# PowerKit.net
KiCad netlist of a schematic drawn in EAGLE
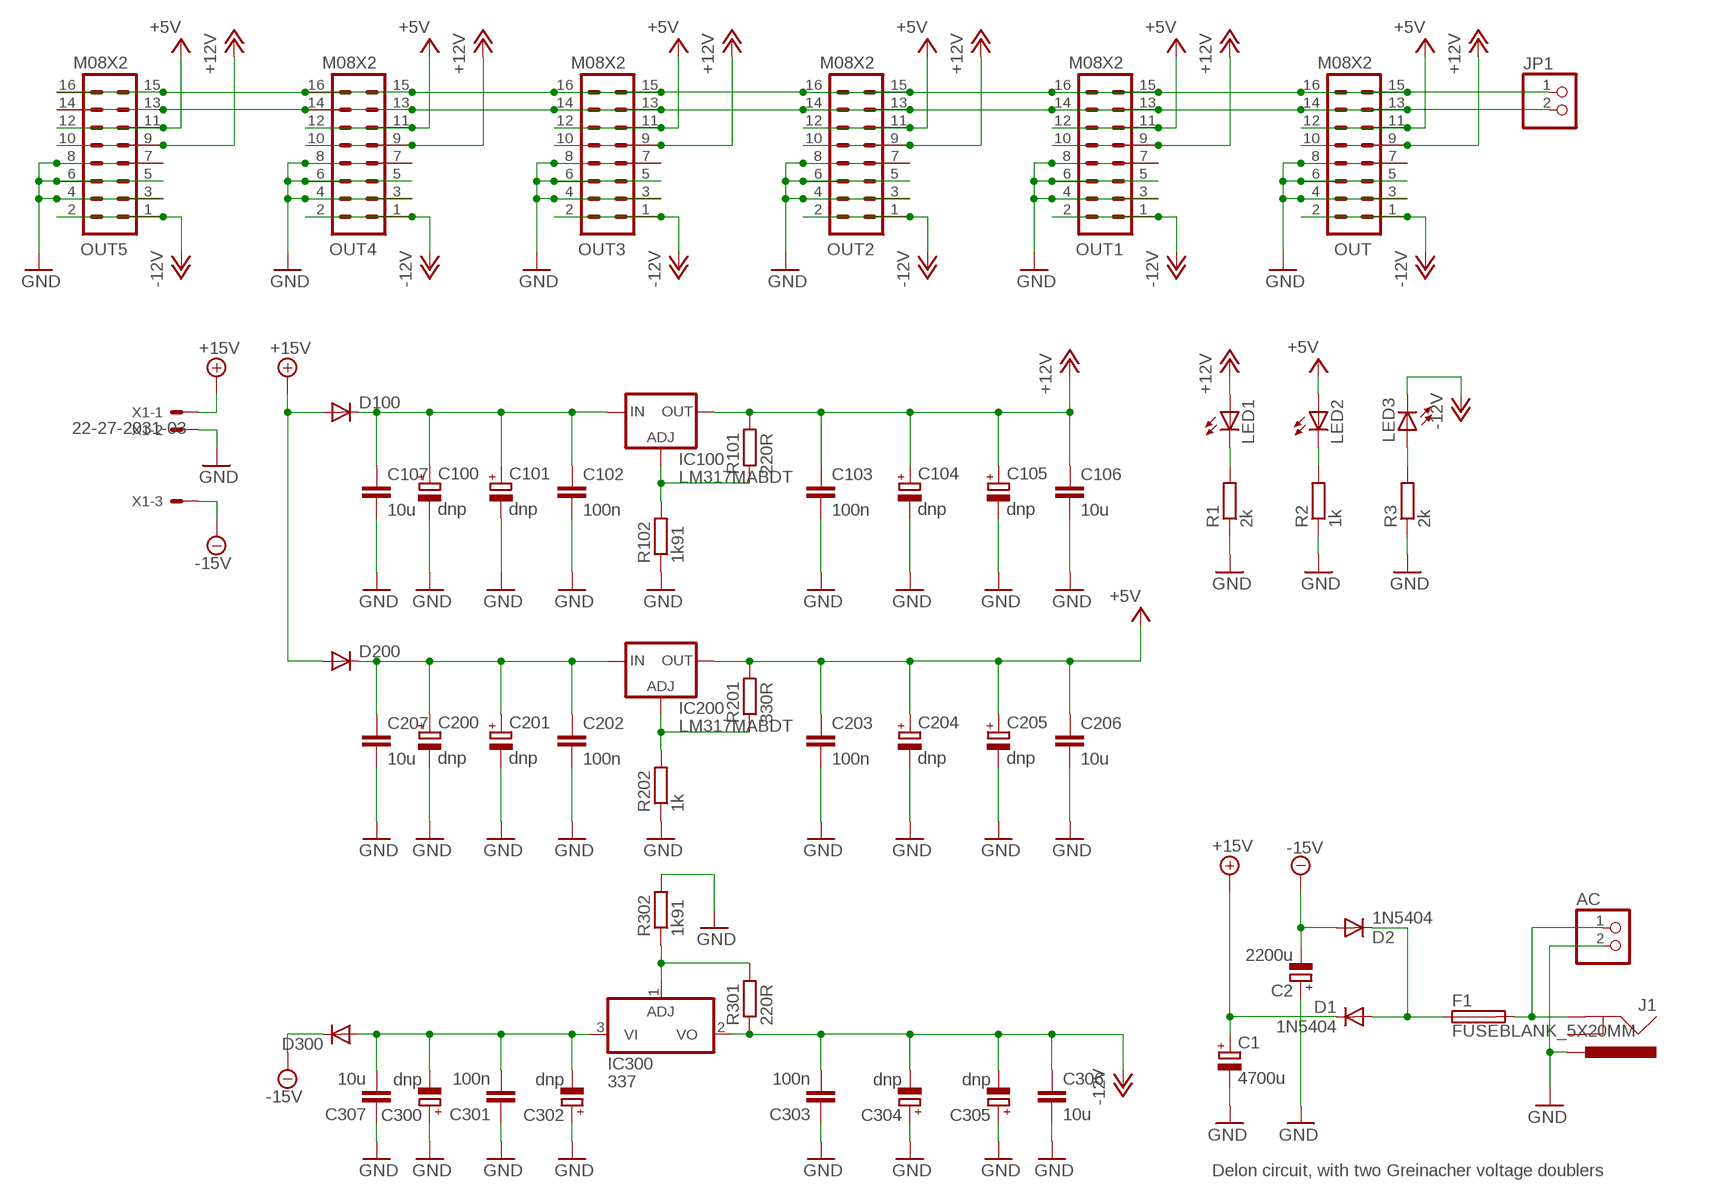
[diagram p0: schematic, sheet 1]

(export (version "E")
  (design (tool "Eeschema 10.0.6"))
  (components
    (comp (ref "AC")
      (value "PINHD-1X2")
      (footprint "eagle-import:1X02")
      (libsource (lib "eagle-import") (part "PINHD-1X2"))
    )
    (comp (ref "C1")
      (value "4700u")
      (footprint "eagle-import:E7,5-18")
      (libsource (lib "eagle-import") (part "resistor_CPOL-EUE7.5-18"))
    )
    (comp (ref "C2")
      (value "2200u")
      (footprint "eagle-import:E7,5-18")
      (libsource (lib "eagle-import") (part "resistor_CPOL-EUE7.5-18"))
    )
    (comp (ref "C100")
      (value "dnp")
      (footprint "eagle-import:E5-8,5")
      (libsource (lib "eagle-import") (part "CPOL-EUE5-8.5"))
    )
    (comp (ref "C101")
      (value "dnp")
      (footprint "eagle-import:153CLV-0810")
      (libsource (lib "eagle-import") (part "CPOL-EU153CLV-0810"))
    )
    (comp (ref "C102")
      (value "100n")
      (footprint "eagle-import:C0603")
      (libsource (lib "eagle-import") (part "C-EUC0603"))
    )
    (comp (ref "C103")
      (value "100n")
      (footprint "eagle-import:C0603")
      (libsource (lib "eagle-import") (part "C-EUC0603"))
    )
    (comp (ref "C104")
      (value "dnp")
      (footprint "eagle-import:153CLV-0810")
      (libsource (lib "eagle-import") (part "CPOL-EU153CLV-0810"))
    )
    (comp (ref "C105")
      (value "dnp")
      (footprint "eagle-import:E5-8,5")
      (libsource (lib "eagle-import") (part "CPOL-EUE5-8.5"))
    )
    (comp (ref "C106")
      (value "10u")
      (footprint "eagle-import:C1206")
      (libsource (lib "eagle-import") (part "C-EUC1206"))
    )
    (comp (ref "C107")
      (value "10u")
      (footprint "eagle-import:C1206")
      (libsource (lib "eagle-import") (part "C-EUC1206"))
    )
    (comp (ref "C200")
      (value "dnp")
      (footprint "eagle-import:E5-8,5")
      (libsource (lib "eagle-import") (part "CPOL-EUE5-8.5"))
    )
    (comp (ref "C201")
      (value "dnp")
      (footprint "eagle-import:153CLV-0810")
      (libsource (lib "eagle-import") (part "CPOL-EU153CLV-0810"))
    )
    (comp (ref "C202")
      (value "100n")
      (footprint "eagle-import:C0603")
      (libsource (lib "eagle-import") (part "C-EUC0603"))
    )
    (comp (ref "C203")
      (value "100n")
      (footprint "eagle-import:C0603")
      (libsource (lib "eagle-import") (part "C-EUC0603"))
    )
    (comp (ref "C204")
      (value "dnp")
      (footprint "eagle-import:153CLV-0810")
      (libsource (lib "eagle-import") (part "CPOL-EU153CLV-0810"))
    )
    (comp (ref "C205")
      (value "dnp")
      (footprint "eagle-import:E5-8,5")
      (libsource (lib "eagle-import") (part "CPOL-EUE5-8.5"))
    )
    (comp (ref "C206")
      (value "10u")
      (footprint "eagle-import:C1206")
      (libsource (lib "eagle-import") (part "C-EUC1206"))
    )
    (comp (ref "C207")
      (value "10u")
      (footprint "eagle-import:C1206")
      (libsource (lib "eagle-import") (part "C-EUC1206"))
    )
    (comp (ref "C300")
      (value "dnp")
      (footprint "eagle-import:E5-8,5")
      (libsource (lib "eagle-import") (part "CPOL-EUE5-8.5"))
    )
    (comp (ref "C301")
      (value "100n")
      (footprint "eagle-import:C0603")
      (libsource (lib "eagle-import") (part "C-EUC0603"))
    )
    (comp (ref "C302")
      (value "dnp")
      (footprint "eagle-import:153CLV-0810")
      (libsource (lib "eagle-import") (part "CPOL-EU153CLV-0810"))
    )
    (comp (ref "C303")
      (value "100n")
      (footprint "eagle-import:C0603")
      (libsource (lib "eagle-import") (part "C-EUC0603"))
    )
    (comp (ref "C304")
      (value "dnp")
      (footprint "eagle-import:153CLV-0810")
      (libsource (lib "eagle-import") (part "CPOL-EU153CLV-0810"))
    )
    (comp (ref "C305")
      (value "dnp")
      (footprint "eagle-import:E5-8,5")
      (libsource (lib "eagle-import") (part "CPOL-EUE5-8.5"))
    )
    (comp (ref "C306")
      (value "10u")
      (footprint "eagle-import:C1206")
      (libsource (lib "eagle-import") (part "C-EUC1206"))
    )
    (comp (ref "C307")
      (value "10u")
      (footprint "eagle-import:C1206")
      (libsource (lib "eagle-import") (part "C-EUC1206"))
    )
    (comp (ref "D1")
      (value "1N5404")
      (footprint "eagle-import:DIODE-1N4001")
      (libsource (lib "eagle-import") (part "DIODE1N4001"))
    )
    (comp (ref "D2")
      (value "1N5404")
      (footprint "eagle-import:DIODE-1N4001")
      (libsource (lib "eagle-import") (part "DIODE1N4001"))
    )
    (comp (ref "D100")
      (value "DIODESMA")
      (footprint "eagle-import:SMA-DIODE")
      (libsource (lib "eagle-import") (part "DIODESMA"))
    )
    (comp (ref "D200")
      (value "DIODESMA")
      (footprint "eagle-import:SMA-DIODE")
      (libsource (lib "eagle-import") (part "DIODESMA"))
    )
    (comp (ref "D300")
      (value "DIODESMA")
      (footprint "eagle-import:SMA-DIODE")
      (libsource (lib "eagle-import") (part "DIODESMA"))
    )
    (comp (ref "F1")
      (value "FUSEBLANK_5X20MM")
      (footprint "eagle-import:FUSE_HOLDER_5X20MM")
      (libsource (lib "eagle-import") (part "FUSEBLANK_5X20MM"))
    )
    (comp (ref "IC100")
      (value "LM317MABDT")
      (footprint "eagle-import:DPACK")
      (libsource (lib "eagle-import") (part "v-reg_LM317?MABDT"))
    )
    (comp (ref "IC200")
      (value "LM317MABDT")
      (footprint "eagle-import:DPACK")
      (libsource (lib "eagle-import") (part "v-reg_LM317?MABDT"))
    )
    (comp (ref "IC300")
      (value "337")
      (footprint "eagle-import:TO252")
      (libsource (lib "eagle-import") (part "337"))
    )
    (comp (ref "J1")
      (value "POWER_JACKPTH")
      (footprint "eagle-import:POWER_JACK_PTH")
      (libsource (lib "eagle-import") (part "POWER_JACKPTH"))
    )
    (comp (ref "JP1")
      (value "PINHD-1X2")
      (footprint "eagle-import:1X02")
      (libsource (lib "eagle-import") (part "PINHD-1X2"))
    )
    (comp (ref "LED1")
      (value "LEDCHIPLED_1206")
      (footprint "eagle-import:CHIPLED_1206")
      (libsource (lib "eagle-import") (part "LEDCHIPLED_1206"))
    )
    (comp (ref "LED2")
      (value "LEDCHIPLED_1206")
      (footprint "eagle-import:CHIPLED_1206")
      (libsource (lib "eagle-import") (part "LEDCHIPLED_1206"))
    )
    (comp (ref "LED3")
      (value "LEDCHIPLED_1206")
      (footprint "eagle-import:CHIPLED_1206")
      (libsource (lib "eagle-import") (part "LEDCHIPLED_1206"))
    )
    (comp (ref "OUT")
      (value "M08X2")
      (footprint "eagle-import:2X8")
      (libsource (lib "eagle-import") (part "M08X2"))
    )
    (comp (ref "OUT1")
      (value "M08X2")
      (footprint "eagle-import:2X8")
      (libsource (lib "eagle-import") (part "M08X2"))
    )
    (comp (ref "OUT2")
      (value "M08X2")
      (footprint "eagle-import:2X8")
      (libsource (lib "eagle-import") (part "M08X2"))
    )
    (comp (ref "OUT3")
      (value "M08X2")
      (footprint "eagle-import:2X8")
      (libsource (lib "eagle-import") (part "M08X2"))
    )
    (comp (ref "OUT4")
      (value "M08X2")
      (footprint "eagle-import:2X8")
      (libsource (lib "eagle-import") (part "M08X2"))
    )
    (comp (ref "OUT5")
      (value "M08X2")
      (footprint "eagle-import:2X8")
      (libsource (lib "eagle-import") (part "M08X2"))
    )
    (comp (ref "R1")
      (value "2k")
      (footprint "eagle-import:0603")
      (libsource (lib "eagle-import") (part "R-EU_0603"))
    )
    (comp (ref "R2")
      (value "1k")
      (footprint "eagle-import:0603")
      (libsource (lib "eagle-import") (part "R-EU_0603"))
    )
    (comp (ref "R3")
      (value "2k")
      (footprint "eagle-import:0603")
      (libsource (lib "eagle-import") (part "R-EU_0603"))
    )
    (comp (ref "R101")
      (value "220R")
      (footprint "eagle-import:0603")
      (libsource (lib "eagle-import") (part "R-EU_0603"))
    )
    (comp (ref "R102")
      (value "1k91")
      (footprint "eagle-import:0603")
      (libsource (lib "eagle-import") (part "R-EU_0603"))
    )
    (comp (ref "R201")
      (value "330R")
      (footprint "eagle-import:0603")
      (libsource (lib "eagle-import") (part "R-EU_0603"))
    )
    (comp (ref "R202")
      (value "1k")
      (footprint "eagle-import:0603")
      (libsource (lib "eagle-import") (part "R-EU_0603"))
    )
    (comp (ref "R301")
      (value "220R")
      (footprint "eagle-import:0603")
      (libsource (lib "eagle-import") (part "R-EU_0603"))
    )
    (comp (ref "R302")
      (value "1k91")
      (footprint "eagle-import:0603")
      (libsource (lib "eagle-import") (part "R-EU_0603"))
    )
    (comp (ref "X1")
      (value "22-27-2031-03")
      (footprint "eagle-import:6410-03")
      (libsource (lib "eagle-import") (part "22-?-0327-2031"))
    )
  )
  (nets
    (net (code "1") (name "+5V") (class "Default")
      (node (ref "C203") (pin "1") (pinfunction "1_1") (pintype "passive"))
      (node (ref "C204") (pin "+") (pinfunction "+_+") (pintype "passive"))
      (node (ref "C205") (pin "+") (pinfunction "+_+") (pintype "passive"))
      (node (ref "C206") (pin "1") (pinfunction "1_1") (pintype "passive"))
      (node (ref "IC200") (pin "4") (pinfunction "OUT_4") (pintype "passive"))
      (node (ref "LED2") (pin "A") (pinfunction "A_A") (pintype "passive"))
      (node (ref "OUT") (pin "11") (pinfunction "11_11") (pintype "passive"))
      (node (ref "OUT") (pin "12") (pinfunction "12_12") (pintype "passive"))
      (node (ref "OUT1") (pin "11") (pinfunction "11_11") (pintype "passive"))
      (node (ref "OUT1") (pin "12") (pinfunction "12_12") (pintype "passive"))
      (node (ref "OUT2") (pin "11") (pinfunction "11_11") (pintype "passive"))
      (node (ref "OUT2") (pin "12") (pinfunction "12_12") (pintype "passive"))
      (node (ref "OUT3") (pin "11") (pinfunction "11_11") (pintype "passive"))
      (node (ref "OUT3") (pin "12") (pinfunction "12_12") (pintype "passive"))
      (node (ref "OUT4") (pin "11") (pinfunction "11_11") (pintype "passive"))
      (node (ref "OUT4") (pin "12") (pinfunction "12_12") (pintype "passive"))
      (node (ref "OUT5") (pin "11") (pinfunction "11_11") (pintype "passive"))
      (node (ref "OUT5") (pin "12") (pinfunction "12_12") (pintype "passive"))
      (node (ref "R201") (pin "2") (pinfunction "2_2") (pintype "passive"))
    )
    (net (code "2") (name "+12V") (class "Default")
      (node (ref "C103") (pin "1") (pinfunction "1_1") (pintype "passive"))
      (node (ref "C104") (pin "+") (pinfunction "+_+") (pintype "passive"))
      (node (ref "C105") (pin "+") (pinfunction "+_+") (pintype "passive"))
      (node (ref "C106") (pin "1") (pinfunction "1_1") (pintype "passive"))
      (node (ref "IC100") (pin "4") (pinfunction "OUT_4") (pintype "passive"))
      (node (ref "LED1") (pin "A") (pinfunction "A_A") (pintype "passive"))
      (node (ref "OUT") (pin "10") (pinfunction "10_10") (pintype "passive"))
      (node (ref "OUT") (pin "9") (pinfunction "9_9") (pintype "passive"))
      (node (ref "OUT1") (pin "10") (pinfunction "10_10") (pintype "passive"))
      (node (ref "OUT1") (pin "9") (pinfunction "9_9") (pintype "passive"))
      (node (ref "OUT2") (pin "10") (pinfunction "10_10") (pintype "passive"))
      (node (ref "OUT2") (pin "9") (pinfunction "9_9") (pintype "passive"))
      (node (ref "OUT3") (pin "10") (pinfunction "10_10") (pintype "passive"))
      (node (ref "OUT3") (pin "9") (pinfunction "9_9") (pintype "passive"))
      (node (ref "OUT4") (pin "10") (pinfunction "10_10") (pintype "passive"))
      (node (ref "OUT4") (pin "9") (pinfunction "9_9") (pintype "passive"))
      (node (ref "OUT5") (pin "10") (pinfunction "10_10") (pintype "passive"))
      (node (ref "OUT5") (pin "9") (pinfunction "9_9") (pintype "passive"))
      (node (ref "R101") (pin "2") (pinfunction "2_2") (pintype "passive"))
    )
    (net (code "3") (name "+15V") (class "Default")
      (node (ref "C1") (pin "+") (pinfunction "+_+") (pintype "passive"))
      (node (ref "D1") (pin "C") (pinfunction "C_C") (pintype "passive"))
      (node (ref "D100") (pin "A") (pinfunction "A_A") (pintype "passive"))
      (node (ref "D200") (pin "A") (pinfunction "A_A") (pintype "passive"))
      (node (ref "X1") (pin "1") (pinfunction "S_1") (pintype "passive"))
    )
    (net (code "4") (name "-12V") (class "Default")
      (node (ref "C303") (pin "2") (pinfunction "2_2") (pintype "passive"))
      (node (ref "C304") (pin "-") (pinfunction "-_-") (pintype "passive"))
      (node (ref "C305") (pin "-") (pinfunction "-_-") (pintype "passive"))
      (node (ref "C306") (pin "1") (pinfunction "1_1") (pintype "passive"))
      (node (ref "IC300") (pin "2") (pinfunction "VO_2") (pintype "passive"))
      (node (ref "LED3") (pin "C") (pinfunction "C_C") (pintype "passive"))
      (node (ref "OUT") (pin "1") (pinfunction "1_1") (pintype "passive"))
      (node (ref "OUT") (pin "2") (pinfunction "2_2") (pintype "passive"))
      (node (ref "OUT1") (pin "1") (pinfunction "1_1") (pintype "passive"))
      (node (ref "OUT1") (pin "2") (pinfunction "2_2") (pintype "passive"))
      (node (ref "OUT2") (pin "1") (pinfunction "1_1") (pintype "passive"))
      (node (ref "OUT2") (pin "2") (pinfunction "2_2") (pintype "passive"))
      (node (ref "OUT3") (pin "1") (pinfunction "1_1") (pintype "passive"))
      (node (ref "OUT3") (pin "2") (pinfunction "2_2") (pintype "passive"))
      (node (ref "OUT4") (pin "1") (pinfunction "1_1") (pintype "passive"))
      (node (ref "OUT4") (pin "2") (pinfunction "2_2") (pintype "passive"))
      (node (ref "OUT5") (pin "1") (pinfunction "1_1") (pintype "passive"))
      (node (ref "OUT5") (pin "2") (pinfunction "2_2") (pintype "passive"))
      (node (ref "R301") (pin "1") (pinfunction "1_1") (pintype "passive"))
    )
    (net (code "5") (name "-15V") (class "Default")
      (node (ref "C2") (pin "-") (pinfunction "-_-") (pintype "passive"))
      (node (ref "D2") (pin "A") (pinfunction "A_A") (pintype "passive"))
      (node (ref "D300") (pin "C") (pinfunction "C_C") (pintype "passive"))
      (node (ref "X1") (pin "3") (pinfunction "S_3") (pintype "passive"))
    )
    (net (code "6") (name "GND") (class "Default")
      (node (ref "AC") (pin "2") (pinfunction "2_2") (pintype "passive"))
      (node (ref "C1") (pin "-") (pinfunction "-_-") (pintype "passive"))
      (node (ref "C100") (pin "-") (pinfunction "-_-") (pintype "passive"))
      (node (ref "C101") (pin "-") (pinfunction "-_-") (pintype "passive"))
      (node (ref "C102") (pin "2") (pinfunction "2_2") (pintype "passive"))
      (node (ref "C103") (pin "2") (pinfunction "2_2") (pintype "passive"))
      (node (ref "C104") (pin "-") (pinfunction "-_-") (pintype "passive"))
      (node (ref "C105") (pin "-") (pinfunction "-_-") (pintype "passive"))
      (node (ref "C106") (pin "2") (pinfunction "2_2") (pintype "passive"))
      (node (ref "C107") (pin "2") (pinfunction "2_2") (pintype "passive"))
      (node (ref "C2") (pin "+") (pinfunction "+_+") (pintype "passive"))
      (node (ref "C200") (pin "-") (pinfunction "-_-") (pintype "passive"))
      (node (ref "C201") (pin "-") (pinfunction "-_-") (pintype "passive"))
      (node (ref "C202") (pin "2") (pinfunction "2_2") (pintype "passive"))
      (node (ref "C203") (pin "2") (pinfunction "2_2") (pintype "passive"))
      (node (ref "C204") (pin "-") (pinfunction "-_-") (pintype "passive"))
      (node (ref "C205") (pin "-") (pinfunction "-_-") (pintype "passive"))
      (node (ref "C206") (pin "2") (pinfunction "2_2") (pintype "passive"))
      (node (ref "C207") (pin "2") (pinfunction "2_2") (pintype "passive"))
      (node (ref "C300") (pin "+") (pinfunction "+_+") (pintype "passive"))
      (node (ref "C301") (pin "1") (pinfunction "1_1") (pintype "passive"))
      (node (ref "C302") (pin "+") (pinfunction "+_+") (pintype "passive"))
      (node (ref "C303") (pin "1") (pinfunction "1_1") (pintype "passive"))
      (node (ref "C304") (pin "+") (pinfunction "+_+") (pintype "passive"))
      (node (ref "C305") (pin "+") (pinfunction "+_+") (pintype "passive"))
      (node (ref "C306") (pin "2") (pinfunction "2_2") (pintype "passive"))
      (node (ref "C307") (pin "1") (pinfunction "1_1") (pintype "passive"))
      (node (ref "J1") (pin "PWR") (pinfunction "PWR_PWR") (pintype "bidirectional"))
      (node (ref "OUT") (pin "3") (pinfunction "3_3") (pintype "passive"))
      (node (ref "OUT") (pin "4") (pinfunction "4_4") (pintype "passive"))
      (node (ref "OUT") (pin "5") (pinfunction "5_5") (pintype "passive"))
      (node (ref "OUT") (pin "6") (pinfunction "6_6") (pintype "passive"))
      (node (ref "OUT") (pin "7") (pinfunction "7_7") (pintype "passive"))
      (node (ref "OUT") (pin "8") (pinfunction "8_8") (pintype "passive"))
      (node (ref "OUT1") (pin "3") (pinfunction "3_3") (pintype "passive"))
      (node (ref "OUT1") (pin "4") (pinfunction "4_4") (pintype "passive"))
      (node (ref "OUT1") (pin "5") (pinfunction "5_5") (pintype "passive"))
      (node (ref "OUT1") (pin "6") (pinfunction "6_6") (pintype "passive"))
      (node (ref "OUT1") (pin "7") (pinfunction "7_7") (pintype "passive"))
      (node (ref "OUT1") (pin "8") (pinfunction "8_8") (pintype "passive"))
      (node (ref "OUT2") (pin "3") (pinfunction "3_3") (pintype "passive"))
      (node (ref "OUT2") (pin "4") (pinfunction "4_4") (pintype "passive"))
      (node (ref "OUT2") (pin "5") (pinfunction "5_5") (pintype "passive"))
      (node (ref "OUT2") (pin "6") (pinfunction "6_6") (pintype "passive"))
      (node (ref "OUT2") (pin "7") (pinfunction "7_7") (pintype "passive"))
      (node (ref "OUT2") (pin "8") (pinfunction "8_8") (pintype "passive"))
      (node (ref "OUT3") (pin "3") (pinfunction "3_3") (pintype "passive"))
      (node (ref "OUT3") (pin "4") (pinfunction "4_4") (pintype "passive"))
      (node (ref "OUT3") (pin "5") (pinfunction "5_5") (pintype "passive"))
      (node (ref "OUT3") (pin "6") (pinfunction "6_6") (pintype "passive"))
      (node (ref "OUT3") (pin "7") (pinfunction "7_7") (pintype "passive"))
      (node (ref "OUT3") (pin "8") (pinfunction "8_8") (pintype "passive"))
      (node (ref "OUT4") (pin "3") (pinfunction "3_3") (pintype "passive"))
      (node (ref "OUT4") (pin "4") (pinfunction "4_4") (pintype "passive"))
      (node (ref "OUT4") (pin "5") (pinfunction "5_5") (pintype "passive"))
      (node (ref "OUT4") (pin "6") (pinfunction "6_6") (pintype "passive"))
      (node (ref "OUT4") (pin "7") (pinfunction "7_7") (pintype "passive"))
      (node (ref "OUT4") (pin "8") (pinfunction "8_8") (pintype "passive"))
      (node (ref "OUT5") (pin "3") (pinfunction "3_3") (pintype "passive"))
      (node (ref "OUT5") (pin "4") (pinfunction "4_4") (pintype "passive"))
      (node (ref "OUT5") (pin "5") (pinfunction "5_5") (pintype "passive"))
      (node (ref "OUT5") (pin "6") (pinfunction "6_6") (pintype "passive"))
      (node (ref "OUT5") (pin "7") (pinfunction "7_7") (pintype "passive"))
      (node (ref "OUT5") (pin "8") (pinfunction "8_8") (pintype "passive"))
      (node (ref "R1") (pin "1") (pinfunction "1_1") (pintype "passive"))
      (node (ref "R102") (pin "1") (pinfunction "1_1") (pintype "passive"))
      (node (ref "R2") (pin "1") (pinfunction "1_1") (pintype "passive"))
      (node (ref "R202") (pin "1") (pinfunction "1_1") (pintype "passive"))
      (node (ref "R3") (pin "1") (pinfunction "1_1") (pintype "passive"))
      (node (ref "R302") (pin "2") (pinfunction "2_2") (pintype "passive"))
      (node (ref "X1") (pin "2") (pinfunction "S_2") (pintype "passive"))
    )
    (net (code "7") (name "Net-(AC-Pad1)") (class "Default")
      (node (ref "AC") (pin "1") (pinfunction "1_1") (pintype "passive"))
      (node (ref "F1") (pin "2") (pinfunction "2_2") (pintype "passive"))
      (node (ref "J1") (pin "GND") (pinfunction "GND_GND") (pintype "bidirectional"))
    )
    (net (code "8") (name "Net-(D1-PadA)") (class "Default")
      (node (ref "D1") (pin "A") (pinfunction "A_A") (pintype "passive"))
      (node (ref "D2") (pin "C") (pinfunction "C_C") (pintype "passive"))
      (node (ref "F1") (pin "1") (pinfunction "1_1") (pintype "passive"))
    )
    (net (code "9") (name "Net-(IC100-ADJ)") (class "Default")
      (node (ref "IC100") (pin "1") (pinfunction "ADJ_1") (pintype "input"))
      (node (ref "R101") (pin "1") (pinfunction "1_1") (pintype "passive"))
      (node (ref "R102") (pin "2") (pinfunction "2_2") (pintype "passive"))
    )
    (net (code "10") (name "Net-(IC100-IN)") (class "Default")
      (node (ref "C100") (pin "+") (pinfunction "+_+") (pintype "passive"))
      (node (ref "C101") (pin "+") (pinfunction "+_+") (pintype "passive"))
      (node (ref "C102") (pin "1") (pinfunction "1_1") (pintype "passive"))
      (node (ref "C107") (pin "1") (pinfunction "1_1") (pintype "passive"))
      (node (ref "D100") (pin "C") (pinfunction "C_C") (pintype "passive"))
      (node (ref "IC100") (pin "3") (pinfunction "IN_3") (pintype "input"))
    )
    (net (code "11") (name "Net-(IC200-ADJ)") (class "Default")
      (node (ref "IC200") (pin "1") (pinfunction "ADJ_1") (pintype "input"))
      (node (ref "R201") (pin "1") (pinfunction "1_1") (pintype "passive"))
      (node (ref "R202") (pin "2") (pinfunction "2_2") (pintype "passive"))
    )
    (net (code "12") (name "Net-(IC200-IN)") (class "Default")
      (node (ref "C200") (pin "+") (pinfunction "+_+") (pintype "passive"))
      (node (ref "C201") (pin "+") (pinfunction "+_+") (pintype "passive"))
      (node (ref "C202") (pin "1") (pinfunction "1_1") (pintype "passive"))
      (node (ref "C207") (pin "1") (pinfunction "1_1") (pintype "passive"))
      (node (ref "D200") (pin "C") (pinfunction "C_C") (pintype "passive"))
      (node (ref "IC200") (pin "3") (pinfunction "IN_3") (pintype "input"))
    )
    (net (code "13") (name "Net-(IC300-ADJ)") (class "Default")
      (node (ref "IC300") (pin "1") (pinfunction "ADJ_1") (pintype "input"))
      (node (ref "R301") (pin "2") (pinfunction "2_2") (pintype "passive"))
      (node (ref "R302") (pin "1") (pinfunction "1_1") (pintype "passive"))
    )
    (net (code "14") (name "Net-(IC300-VI)") (class "Default")
      (node (ref "C300") (pin "-") (pinfunction "-_-") (pintype "passive"))
      (node (ref "C301") (pin "2") (pinfunction "2_2") (pintype "passive"))
      (node (ref "C302") (pin "-") (pinfunction "-_-") (pintype "passive"))
      (node (ref "C307") (pin "2") (pinfunction "2_2") (pintype "passive"))
      (node (ref "D300") (pin "A") (pinfunction "A_A") (pintype "passive"))
      (node (ref "IC300") (pin "3") (pinfunction "VI_3") (pintype "input"))
    )
    (net (code "15") (name "Net-(JP1-Pad1)") (class "Default")
      (node (ref "JP1") (pin "1") (pinfunction "1_1") (pintype "passive"))
      (node (ref "OUT") (pin "15") (pinfunction "15_15") (pintype "passive"))
      (node (ref "OUT") (pin "16") (pinfunction "16_16") (pintype "passive"))
      (node (ref "OUT1") (pin "15") (pinfunction "15_15") (pintype "passive"))
      (node (ref "OUT1") (pin "16") (pinfunction "16_16") (pintype "passive"))
      (node (ref "OUT2") (pin "15") (pinfunction "15_15") (pintype "passive"))
      (node (ref "OUT2") (pin "16") (pinfunction "16_16") (pintype "passive"))
      (node (ref "OUT3") (pin "15") (pinfunction "15_15") (pintype "passive"))
      (node (ref "OUT3") (pin "16") (pinfunction "16_16") (pintype "passive"))
      (node (ref "OUT4") (pin "15") (pinfunction "15_15") (pintype "passive"))
      (node (ref "OUT4") (pin "16") (pinfunction "16_16") (pintype "passive"))
      (node (ref "OUT5") (pin "15") (pinfunction "15_15") (pintype "passive"))
      (node (ref "OUT5") (pin "16") (pinfunction "16_16") (pintype "passive"))
    )
    (net (code "16") (name "Net-(JP1-Pad2)") (class "Default")
      (node (ref "JP1") (pin "2") (pinfunction "2_2") (pintype "passive"))
      (node (ref "OUT") (pin "13") (pinfunction "13_13") (pintype "passive"))
      (node (ref "OUT") (pin "14") (pinfunction "14_14") (pintype "passive"))
      (node (ref "OUT1") (pin "13") (pinfunction "13_13") (pintype "passive"))
      (node (ref "OUT1") (pin "14") (pinfunction "14_14") (pintype "passive"))
      (node (ref "OUT2") (pin "13") (pinfunction "13_13") (pintype "passive"))
      (node (ref "OUT2") (pin "14") (pinfunction "14_14") (pintype "passive"))
      (node (ref "OUT3") (pin "13") (pinfunction "13_13") (pintype "passive"))
      (node (ref "OUT3") (pin "14") (pinfunction "14_14") (pintype "passive"))
      (node (ref "OUT4") (pin "13") (pinfunction "13_13") (pintype "passive"))
      (node (ref "OUT4") (pin "14") (pinfunction "14_14") (pintype "passive"))
      (node (ref "OUT5") (pin "13") (pinfunction "13_13") (pintype "passive"))
      (node (ref "OUT5") (pin "14") (pinfunction "14_14") (pintype "passive"))
    )
    (net (code "17") (name "Net-(LED1-PadC)") (class "Default")
      (node (ref "LED1") (pin "C") (pinfunction "C_C") (pintype "passive"))
      (node (ref "R1") (pin "2") (pinfunction "2_2") (pintype "passive"))
    )
    (net (code "18") (name "Net-(LED2-PadC)") (class "Default")
      (node (ref "LED2") (pin "C") (pinfunction "C_C") (pintype "passive"))
      (node (ref "R2") (pin "2") (pinfunction "2_2") (pintype "passive"))
    )
    (net (code "19") (name "Net-(LED3-PadA)") (class "Default")
      (node (ref "LED3") (pin "A") (pinfunction "A_A") (pintype "passive"))
      (node (ref "R3") (pin "2") (pinfunction "2_2") (pintype "passive"))
    )
    (net (code "20") (name "unconnected-(J1-PadGNDBREAK)") (class "Default")
      (node (ref "J1") (pin "GNDBREAK") (pinfunction "GNDBREAK_GNDBREAK") (pintype "bidirectional"))
    )
  )
)
